# Part23_ETH_LAN.net
KiCad netlist of a schematic drawn in Altium Designer
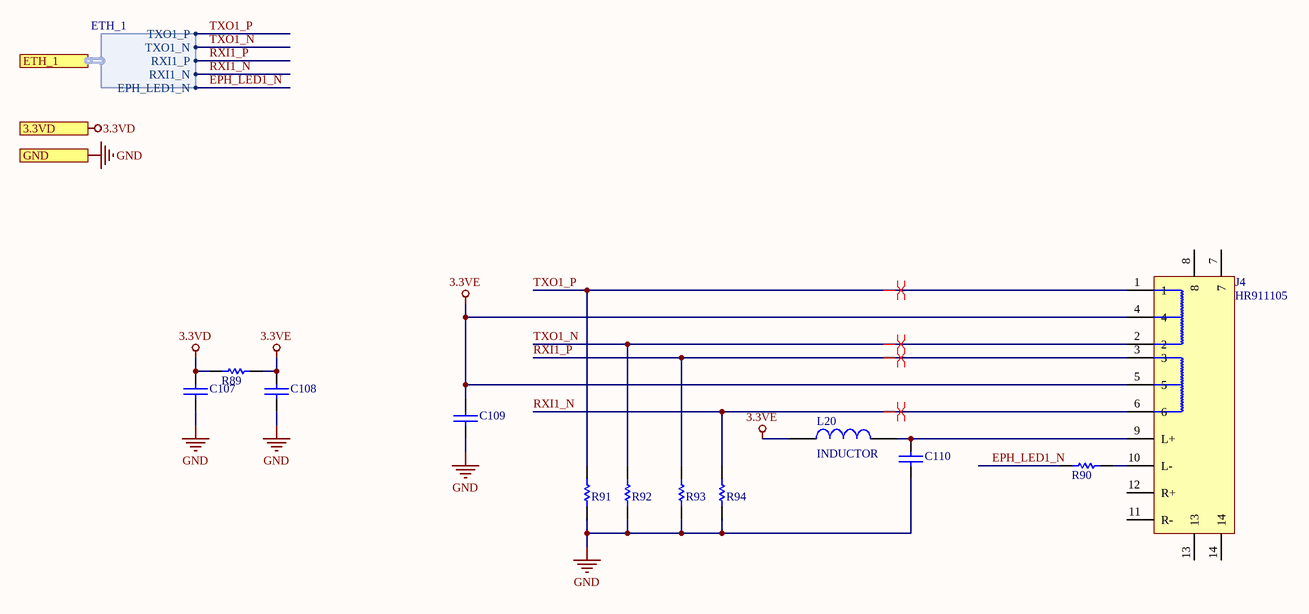
[diagram p0: Part23_ETH_LAN.SchDoc]

(export (version "E")
  (design (tool "Eeschema 10.0.6"))
  (components
    (comp (ref "C107")
      (value "100nF")
      (footprint "0402C")
      (description "无极性电容")
      (libsource (lib "电容") (part "CAP"))
    )
    (comp (ref "C108")
      (value "100nF")
      (footprint "0402C")
      (description "无极性电容")
      (libsource (lib "电容") (part "CAP"))
    )
    (comp (ref "C109")
      (value "100nF")
      (footprint "0402C")
      (description "无极性电容")
      (libsource (lib "电容") (part "CAP"))
    )
    (comp (ref "C110")
      (value "100nF")
      (footprint "0402C")
      (description "无极性电容")
      (libsource (lib "电容") (part "CAP"))
    )
    (comp (ref "J4") (value "HR911105") (footprint "HR911105A") (libsource (lib "网络插座") (part "HR911105")))
    (comp (ref "L20") (value "INDUCTOR") (footprint "0402L") (libsource (lib "电感") (part "INDUCTOR")))
    (comp (ref "R89") (value "0R") (footprint "0402R") (libsource (lib "电阻") (part "RES")))
    (comp (ref "R90") (value "1K") (footprint "0402R") (libsource (lib "电阻") (part "RES")))
    (comp (ref "R91") (value "49.9R") (footprint "0402R") (libsource (lib "电阻") (part "RES")))
    (comp (ref "R92") (value "49.9R") (footprint "0402R") (libsource (lib "电阻") (part "RES")))
    (comp (ref "R93") (value "49.9R") (footprint "0402R") (libsource (lib "电阻") (part "RES")))
    (comp (ref "R94") (value "49.9R") (footprint "0402R") (libsource (lib "电阻") (part "RES")))
  )
  (nets
    (net (code "2") (name "/EPH_LED1_N") (class "Default")
      (node (ref "R90") (pin "2") (pinfunction "2_2") (pintype "passive"))
    )
    (net (code "3") (name "/RXI1_N") (class "Default")
      (node (ref "J4") (pin "6") (pinfunction "6_6") (pintype "passive"))
      (node (ref "R94") (pin "2") (pinfunction "2_2") (pintype "passive"))
    )
    (net (code "4") (name "/RXI1_P") (class "Default")
      (node (ref "J4") (pin "3") (pinfunction "3_3") (pintype "passive"))
      (node (ref "R93") (pin "2") (pinfunction "2_2") (pintype "passive"))
    )
    (net (code "5") (name "/TXO1_N") (class "Default")
      (node (ref "J4") (pin "2") (pinfunction "2_2") (pintype "passive"))
      (node (ref "R92") (pin "2") (pinfunction "2_2") (pintype "passive"))
    )
    (net (code "6") (name "/TXO1_P") (class "Default")
      (node (ref "J4") (pin "1") (pinfunction "1_1") (pintype "passive"))
      (node (ref "R91") (pin "2") (pinfunction "2_2") (pintype "passive"))
    )
    (net (code "8") (name "3.3VD") (class "Default")
      (node (ref "C107") (pin "1") (pinfunction "1_1") (pintype "passive"))
      (node (ref "R89") (pin "1") (pinfunction "1_1") (pintype "passive"))
    )
    (net (code "9") (name "3.3VE") (class "Default")
      (node (ref "C108") (pin "1") (pinfunction "1_1") (pintype "passive"))
      (node (ref "C109") (pin "1") (pinfunction "1_1") (pintype "passive"))
      (node (ref "J4") (pin "4") (pinfunction "4_4") (pintype "passive"))
      (node (ref "J4") (pin "5") (pinfunction "5_5") (pintype "passive"))
      (node (ref "L20") (pin "1") (pinfunction "1_1") (pintype "passive"))
      (node (ref "R89") (pin "2") (pinfunction "2_2") (pintype "passive"))
    )
    (net (code "10") (name "GND") (class "Default")
      (node (ref "C107") (pin "2") (pinfunction "2_2") (pintype "passive"))
      (node (ref "C108") (pin "2") (pinfunction "2_2") (pintype "passive"))
      (node (ref "C109") (pin "2") (pinfunction "2_2") (pintype "passive"))
      (node (ref "C110") (pin "2") (pinfunction "2_2") (pintype "passive"))
      (node (ref "R91") (pin "1") (pinfunction "1_1") (pintype "passive"))
      (node (ref "R92") (pin "1") (pinfunction "1_1") (pintype "passive"))
      (node (ref "R93") (pin "1") (pinfunction "1_1") (pintype "passive"))
      (node (ref "R94") (pin "1") (pinfunction "1_1") (pintype "passive"))
    )
    (net (code "11") (name "Net-(J4-L+)") (class "Default")
      (node (ref "C110") (pin "1") (pinfunction "1_1") (pintype "passive"))
      (node (ref "J4") (pin "9") (pinfunction "L+_9") (pintype "passive"))
      (node (ref "L20") (pin "2") (pinfunction "2_2") (pintype "passive"))
    )
    (net (code "12") (name "Net-(J4-L-)") (class "Default")
      (node (ref "J4") (pin "10") (pinfunction "L-_10") (pintype "passive"))
      (node (ref "R90") (pin "1") (pinfunction "1_1") (pintype "passive"))
    )
    (net (code "13") (name "unconnected-(J4-Pad7)") (class "Default")
      (node (ref "J4") (pin "7") (pinfunction "7_7") (pintype "passive"))
    )
    (net (code "14") (name "unconnected-(J4-Pad8)") (class "Default")
      (node (ref "J4") (pin "8") (pinfunction "8_8") (pintype "passive"))
    )
    (net (code "15") (name "unconnected-(J4-Pad13)") (class "Default")
      (node (ref "J4") (pin "13") (pinfunction "13_13") (pintype "passive"))
    )
    (net (code "16") (name "unconnected-(J4-Pad14)") (class "Default")
      (node (ref "J4") (pin "14") (pinfunction "14_14") (pintype "passive"))
    )
    (net (code "17") (name "unconnected-(J4-R+-Pad12)") (class "Default")
      (node (ref "J4") (pin "12") (pinfunction "R+_12") (pintype "passive"))
    )
    (net (code "18") (name "unconnected-(J4-R--Pad11)") (class "Default")
      (node (ref "J4") (pin "11") (pinfunction "R-_11") (pintype "passive"))
    )
  )
)
